# main.net
KiCad netlist of a schematic drawn in Altium Designer
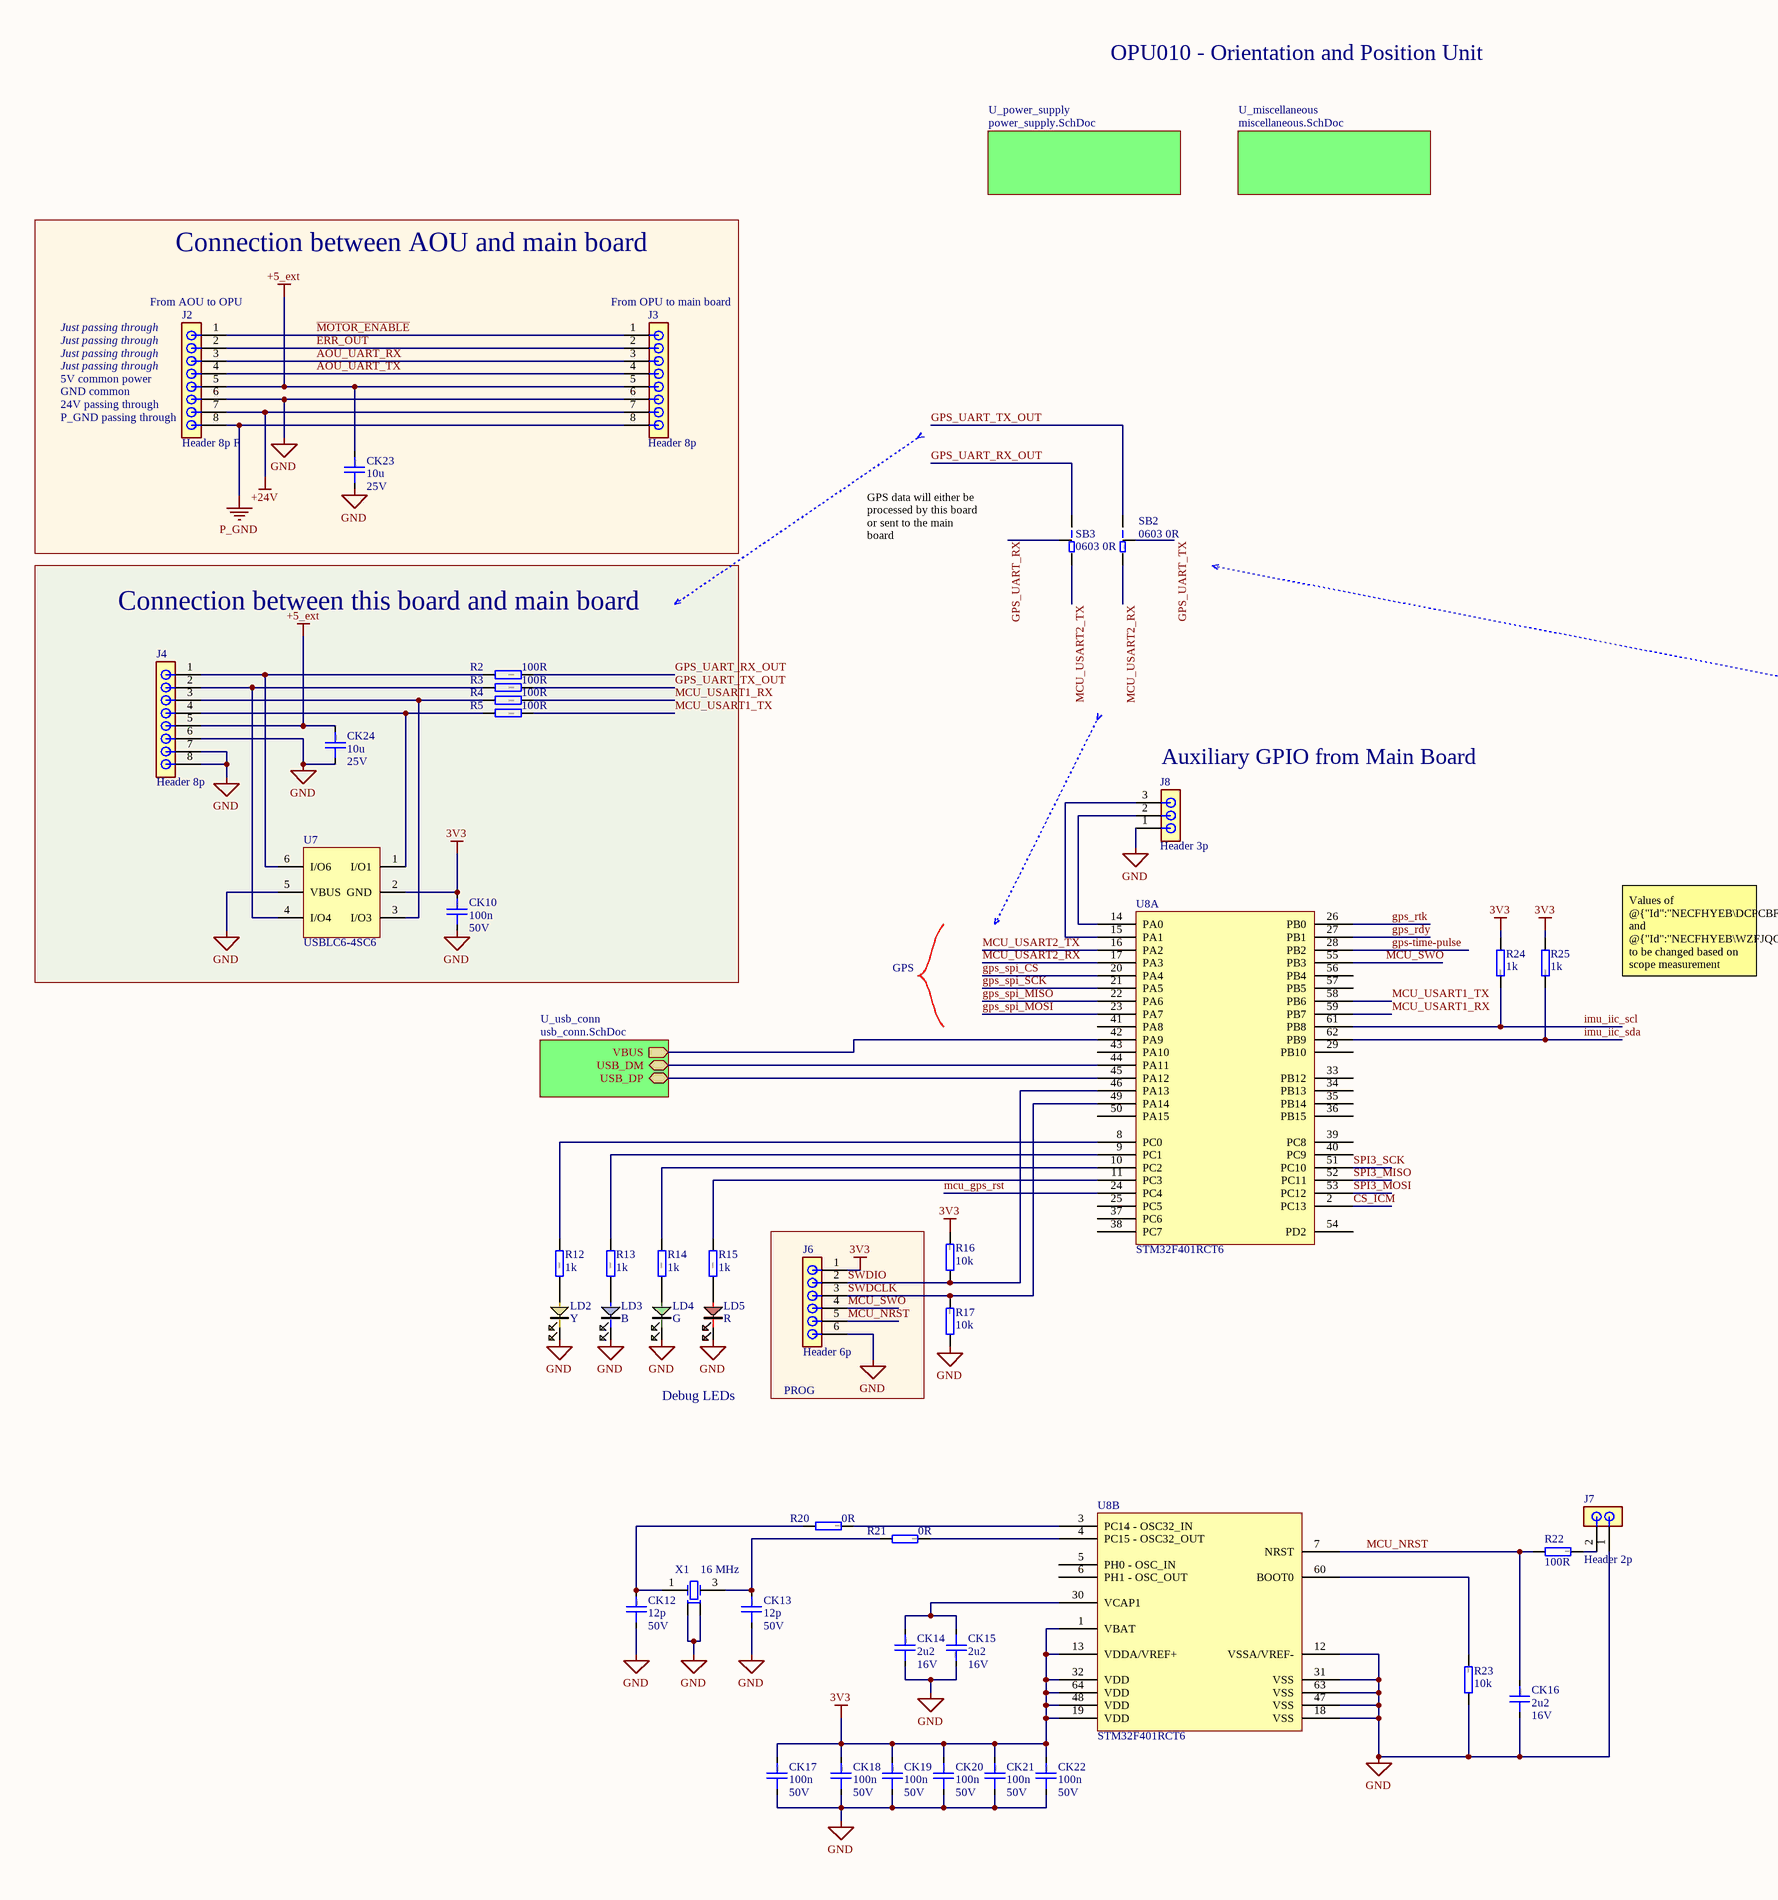
[diagram p0: main.SchDoc, left]
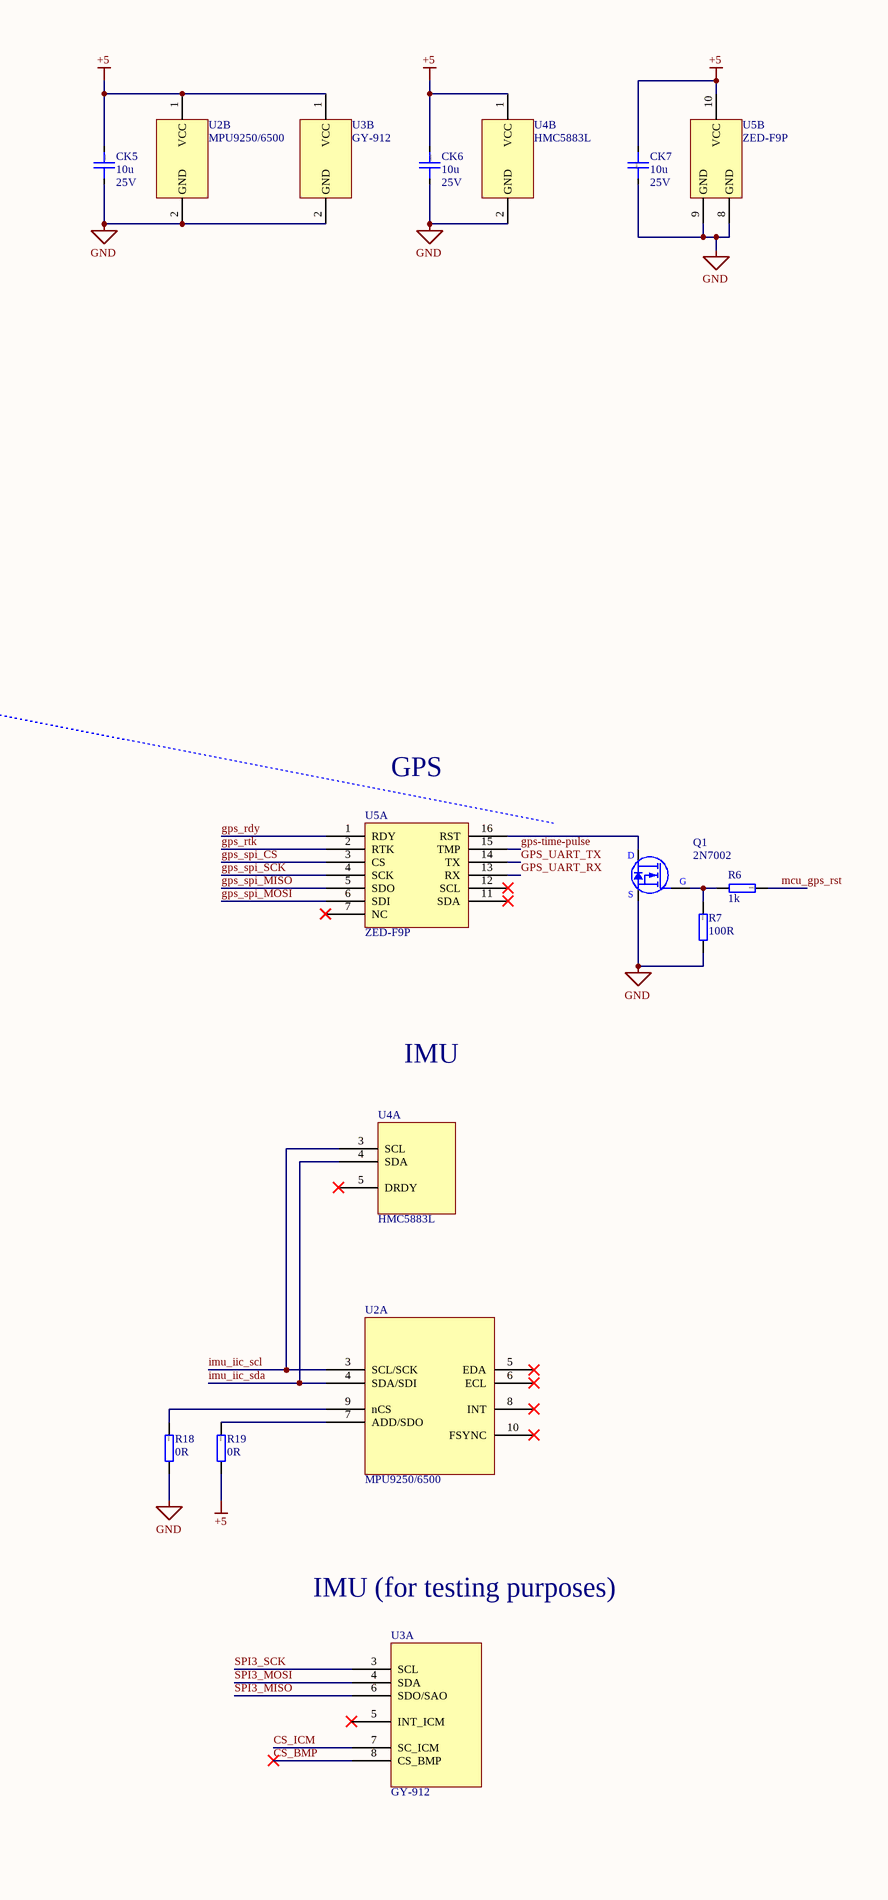
[diagram p1: main.SchDoc, right]

(export (version "E")
  (design (tool "Eeschema 10.0.6"))
  (components
    (comp (ref "CK5")
      (value "10u")
      (footprint "CAP0805")
      (description "25V 10uF X5R ±10% 0805 Multilayer Ceramic Capacitors MLCC - SMD/SMT ROHS")
      (fields (field (name "JLCPCB PART") "C15850") (field (name "VOLTAGE RATING") "25V"))
      (libsource (lib "Kubikova ultra knihovna") (part "Cap 10u 0805"))
    )
    (comp (ref "CK6")
      (value "10u")
      (footprint "CAP0805")
      (description "25V 10uF X5R ±10% 0805 Multilayer Ceramic Capacitors MLCC - SMD/SMT ROHS")
      (fields (field (name "JLCPCB PART") "C15850") (field (name "VOLTAGE RATING") "25V"))
      (libsource (lib "Kubikova ultra knihovna") (part "Cap 10u 0805"))
    )
    (comp (ref "CK7")
      (value "10u")
      (footprint "CAP0805")
      (description "25V 10uF X5R ±10% 0805 Multilayer Ceramic Capacitors MLCC - SMD/SMT ROHS")
      (fields (field (name "JLCPCB PART") "C15850") (field (name "VOLTAGE RATING") "25V"))
      (libsource (lib "Kubikova ultra knihovna") (part "Cap 10u 0805"))
    )
    (comp (ref "CK10")
      (value "100n")
      (footprint "CAP0603")
      (description "50V 100nF X7R ±10% 0603 Multilayer Ceramic Capacitors MLCC - SMD/SMT ROHS")
      (fields (field (name "JLCPCB PART") "C14663") (field (name "VOLTAGE RATING") "50V"))
      (libsource (lib "Kubikova ultra knihovna") (part "Cap 100n 0603"))
    )
    (comp (ref "CK12")
      (value "12p")
      (footprint "CAP0603")
      (description "50V 12pF C0G ±5% 0603 Multilayer Ceramic Capacitors MLCC - SMD/SMT ROHS")
      (fields (field (name "JLCPCB PART") "C38523") (field (name "VOLTAGE RATING") "50V"))
      (libsource (lib "Kubikova ultra knihovna") (part "Cap 12p 0603"))
    )
    (comp (ref "CK13")
      (value "12p")
      (footprint "CAP0603")
      (description "50V 12pF C0G ±5% 0603 Multilayer Ceramic Capacitors MLCC - SMD/SMT ROHS")
      (fields (field (name "JLCPCB PART") "C38523") (field (name "VOLTAGE RATING") "50V"))
      (libsource (lib "Kubikova ultra knihovna") (part "Cap 12p 0603"))
    )
    (comp (ref "CK14")
      (value "2u2")
      (footprint "CAP0603")
      (description "16V 2.2uF X5R ±10% 0603 Multilayer Ceramic Capacitors MLCC - SMD/SMT ROHS")
      (fields (field (name "JLCPCB PART") "C23630") (field (name "VOLTAGE RATING") "16V"))
      (libsource (lib "Kubikova ultra knihovna") (part "Cap 2u2 0603"))
    )
    (comp (ref "CK15")
      (value "2u2")
      (footprint "CAP0603")
      (description "16V 2.2uF X5R ±10% 0603 Multilayer Ceramic Capacitors MLCC - SMD/SMT ROHS")
      (fields (field (name "JLCPCB PART") "C23630") (field (name "VOLTAGE RATING") "16V"))
      (libsource (lib "Kubikova ultra knihovna") (part "Cap 2u2 0603"))
    )
    (comp (ref "CK16")
      (value "2u2")
      (footprint "CAP0603")
      (description "16V 2.2uF X5R ±10% 0603 Multilayer Ceramic Capacitors MLCC - SMD/SMT ROHS")
      (fields (field (name "JLCPCB PART") "C23630") (field (name "VOLTAGE RATING") "16V"))
      (libsource (lib "Kubikova ultra knihovna") (part "Cap 2u2 0603"))
    )
    (comp (ref "CK17")
      (value "100n")
      (footprint "CAP0603")
      (description "50V 100nF X7R ±10% 0603 Multilayer Ceramic Capacitors MLCC - SMD/SMT ROHS")
      (fields (field (name "JLCPCB PART") "C14663") (field (name "VOLTAGE RATING") "50V"))
      (libsource (lib "Kubikova ultra knihovna") (part "Cap 100n 0603"))
    )
    (comp (ref "CK18")
      (value "100n")
      (footprint "CAP0603")
      (description "50V 100nF X7R ±10% 0603 Multilayer Ceramic Capacitors MLCC - SMD/SMT ROHS")
      (fields (field (name "JLCPCB PART") "C14663") (field (name "VOLTAGE RATING") "50V"))
      (libsource (lib "Kubikova ultra knihovna") (part "Cap 100n 0603"))
    )
    (comp (ref "CK19")
      (value "100n")
      (footprint "CAP0603")
      (description "50V 100nF X7R ±10% 0603 Multilayer Ceramic Capacitors MLCC - SMD/SMT ROHS")
      (fields (field (name "JLCPCB PART") "C14663") (field (name "VOLTAGE RATING") "50V"))
      (libsource (lib "Kubikova ultra knihovna") (part "Cap 100n 0603"))
    )
    (comp (ref "CK20")
      (value "100n")
      (footprint "CAP0603")
      (description "50V 100nF X7R ±10% 0603 Multilayer Ceramic Capacitors MLCC - SMD/SMT ROHS")
      (fields (field (name "JLCPCB PART") "C14663") (field (name "VOLTAGE RATING") "50V"))
      (libsource (lib "Kubikova ultra knihovna") (part "Cap 100n 0603"))
    )
    (comp (ref "CK21")
      (value "100n")
      (footprint "CAP0603")
      (description "50V 100nF X7R ±10% 0603 Multilayer Ceramic Capacitors MLCC - SMD/SMT ROHS")
      (fields (field (name "JLCPCB PART") "C14663") (field (name "VOLTAGE RATING") "50V"))
      (libsource (lib "Kubikova ultra knihovna") (part "Cap 100n 0603"))
    )
    (comp (ref "CK22")
      (value "100n")
      (footprint "CAP0603")
      (description "50V 100nF X7R ±10% 0603 Multilayer Ceramic Capacitors MLCC - SMD/SMT ROHS")
      (fields (field (name "JLCPCB PART") "C14663") (field (name "VOLTAGE RATING") "50V"))
      (libsource (lib "Kubikova ultra knihovna") (part "Cap 100n 0603"))
    )
    (comp (ref "CK23")
      (value "10u")
      (footprint "CAP0805")
      (description "25V 10uF X5R ±10% 0805 Multilayer Ceramic Capacitors MLCC - SMD/SMT ROHS")
      (fields (field (name "JLCPCB PART") "C15850") (field (name "VOLTAGE RATING") "25V"))
      (libsource (lib "Kubikova ultra knihovna") (part "Cap 10u 0805"))
    )
    (comp (ref "CK24")
      (value "10u")
      (footprint "CAP0805")
      (description "25V 10uF X5R ±10% 0805 Multilayer Ceramic Capacitors MLCC - SMD/SMT ROHS")
      (fields (field (name "JLCPCB PART") "C15850") (field (name "VOLTAGE RATING") "25V"))
      (libsource (lib "Kubikova ultra knihovna") (part "Cap 10u 0805"))
    )
    (comp (ref "J2")
      (value "Header 8p F")
      (footprint "Pin header 8p - F")
      (fields (field (name "MANUFACTURER_PART_NUMBER") "DS1021-1*2SF11-B"))
      (libsource (lib "Kubikova ultra knihovna") (part "Pin header 8p_F"))
    )
    (comp (ref "J3")
      (value "Header 8p")
      (footprint "Pin header 8p")
      (fields
        (field (name "MANUFACTURER_PART_NUMBER") "DS1021-1*2SF11-B")
        (field (name "JLCPCB PART") "C37208")
      )
      (libsource (lib "Kubikova ultra knihovna") (part "Pin header 8p"))
    )
    (comp (ref "J4")
      (value "Header 8p")
      (footprint "Pin header 8p")
      (fields
        (field (name "MANUFACTURER_PART_NUMBER") "DS1021-1*2SF11-B")
        (field (name "JLCPCB PART") "C37208")
      )
      (libsource (lib "") (part "Pin header 8p_1"))
    )
    (comp (ref "J6")
      (value "Header 6p")
      (footprint "Pin header 6p")
      (fields
        (field (name "MANUFACTURER_PART_NUMBER") "DS1021-1*2SF11-B")
        (field (name "JLCPCB PART") "C37208")
      )
      (libsource (lib "Kubikova ultra knihovna") (part "Pin header 6p"))
    )
    (comp (ref "J7")
      (value "Header 2p")
      (footprint "Pin header 2p")
      (description "Connector")
      (fields
        (field (name "MANUFACTURER_PART_NUMBER") "DS1021-1*2SF11-B")
        (field (name "JLCPCB PART") "C492401")
      )
      (libsource (lib "Kubikova ultra knihovna") (part "Pin header 2p"))
    )
    (comp (ref "J8")
      (value "Header 3p")
      (footprint "Pin header 3p")
      (description "Direct Insert 2.54mm Policy 3A 2.5mm -40℃~+105℃ 3mm 6mm 250V Black 1x3P Single Row 3P Pin Headers")
      (fields
        (field (name "MANUFACTURER_PART_NUMBER") "DS1021-1*2SF11-B")
        (field (name "JLCPCB PART") "C2937625")
      )
      (libsource (lib "Kubikova ultra knihovna") (part "Pin header 3p"))
    )
    (comp (ref "LD2")
      (value "Y")
      (footprint "0603_LED_Y")
      (description "0603 Yellow Led")
      (fields (field (name "JLCPCB PART") "C7496811"))
      (libsource (lib "Kubikova ultra knihovna") (part "LED Y 0603"))
    )
    (comp (ref "LD3")
      (value "B")
      (footprint "0603_LED_B")
      (description "0603 Blue Led")
      (fields (field (name "JLCPCB PART") "C7496819"))
      (libsource (lib "Kubikova ultra knihovna") (part "LED B 0603"))
    )
    (comp (ref "LD4")
      (value "G")
      (footprint "0603_LED_G")
      (description "0603 Green Led")
      (fields (field (name "JLCPCB PART") "C22371297"))
      (libsource (lib "Kubikova ultra knihovna") (part "LED G 0603"))
    )
    (comp (ref "LD5")
      (value "R")
      (footprint "0603_LED_R")
      (description "-40℃~+85℃ Red 0603 LED Indication - Discrete ROHS")
      (fields (field (name "JLCPCB PART") "C2286"))
      (libsource (lib "Kubikova ultra knihovna") (part "LED R 0603"))
    )
    (comp (ref "Q1")
      (value "2N7002")
      (footprint "SOT95P230X110-3N(SOT23)")
      (description "60V 115mA 200mW 7.5Ω@10V,500mA 2.5V@250uA 1 N-Channel SOT-23 MOSFETs ROHS")
      (fields (field (name "JLCPCB PART") "C8545"))
      (libsource (lib "Kubikova ultra knihovna") (part "2N7002"))
    )
    (comp (ref "R2")
      (value "100R")
      (footprint "RESC2012X06N(SMR0805)")
      (description "125mW Thick Film Resistors 150V ±100ppm/℃ ±1% 100Ω 0805 Chip Resistor - Surface Mount ROHS")
      (fields (field (name "JLCPCB PART") "C17408") (field (name "AUTHOR") "JP/27.03.2014"))
      (libsource (lib "Kubikova ultra knihovna") (part "Res 100R 0805"))
    )
    (comp (ref "R3")
      (value "100R")
      (footprint "RESC2012X06N(SMR0805)")
      (description "125mW Thick Film Resistors 150V ±100ppm/℃ ±1% 100Ω 0805 Chip Resistor - Surface Mount ROHS")
      (fields (field (name "JLCPCB PART") "C17408") (field (name "AUTHOR") "JP/27.03.2014"))
      (libsource (lib "Kubikova ultra knihovna") (part "Res 100R 0805"))
    )
    (comp (ref "R4")
      (value "100R")
      (footprint "RESC2012X06N(SMR0805)")
      (description "125mW Thick Film Resistors 150V ±100ppm/℃ ±1% 100Ω 0805 Chip Resistor - Surface Mount ROHS")
      (fields (field (name "JLCPCB PART") "C17408") (field (name "AUTHOR") "JP/27.03.2014"))
      (libsource (lib "Kubikova ultra knihovna") (part "Res 100R 0805"))
    )
    (comp (ref "R5")
      (value "100R")
      (footprint "RESC2012X06N(SMR0805)")
      (description "125mW Thick Film Resistors 150V ±100ppm/℃ ±1% 100Ω 0805 Chip Resistor - Surface Mount ROHS")
      (fields (field (name "JLCPCB PART") "C17408") (field (name "AUTHOR") "JP/27.03.2014"))
      (libsource (lib "Kubikova ultra knihovna") (part "Res 100R 0805"))
    )
    (comp (ref "R6")
      (value "1k")
      (footprint "RESC2012X06N(SMR0805)")
      (description "125mW Thick Film Resistors 150V ±100ppm/℃ ±1% 1kΩ 0805 Chip Resistor - Surface Mount ROHS")
      (fields (field (name "JLCPCB PART") "C17513") (field (name "AUTHOR") "JP/27.03.2014"))
      (libsource (lib "Kubikova ultra knihovna") (part "Res 1k 0805"))
    )
    (comp (ref "R7")
      (value "100R")
      (footprint "RESC2012X06N(SMR0805)")
      (description "125mW Thick Film Resistors 150V ±100ppm/℃ ±1% 100Ω 0805 Chip Resistor - Surface Mount ROHS")
      (fields (field (name "JLCPCB PART") "C17408") (field (name "AUTHOR") "JP/27.03.2014"))
      (libsource (lib "Kubikova ultra knihovna") (part "Res 100R 0805"))
    )
    (comp (ref "R12")
      (value "1k")
      (footprint "RESC2012X06N(SMR0805)")
      (description "125mW Thick Film Resistors 150V ±100ppm/℃ ±1% 1kΩ 0805 Chip Resistor - Surface Mount ROHS")
      (fields (field (name "JLCPCB PART") "C17513") (field (name "AUTHOR") "JP/27.03.2014"))
      (libsource (lib "Kubikova ultra knihovna") (part "Res 1k 0805"))
    )
    (comp (ref "R13")
      (value "1k")
      (footprint "RESC2012X06N(SMR0805)")
      (description "125mW Thick Film Resistors 150V ±100ppm/℃ ±1% 1kΩ 0805 Chip Resistor - Surface Mount ROHS")
      (fields (field (name "JLCPCB PART") "C17513") (field (name "AUTHOR") "JP/27.03.2014"))
      (libsource (lib "Kubikova ultra knihovna") (part "Res 1k 0805"))
    )
    (comp (ref "R14")
      (value "1k")
      (footprint "RESC2012X06N(SMR0805)")
      (description "125mW Thick Film Resistors 150V ±100ppm/℃ ±1% 1kΩ 0805 Chip Resistor - Surface Mount ROHS")
      (fields (field (name "JLCPCB PART") "C17513") (field (name "AUTHOR") "JP/27.03.2014"))
      (libsource (lib "Kubikova ultra knihovna") (part "Res 1k 0805"))
    )
    (comp (ref "R15")
      (value "1k")
      (footprint "RESC2012X06N(SMR0805)")
      (description "125mW Thick Film Resistors 150V ±100ppm/℃ ±1% 1kΩ 0805 Chip Resistor - Surface Mount ROHS")
      (fields (field (name "JLCPCB PART") "C17513") (field (name "AUTHOR") "JP/27.03.2014"))
      (libsource (lib "Kubikova ultra knihovna") (part "Res 1k 0805"))
    )
    (comp (ref "R16")
      (value "10k")
      (footprint "RESC2012X06N(SMR0805)")
      (description "125mW Thick Film Resistors 150V ±100ppm/℃ ±1% 10kΩ 0805 Chip Resistor - Surface Mount ROHS")
      (fields (field (name "JLCPCB PART") "C17414"))
      (libsource (lib "Kubikova ultra knihovna") (part "Res 10k 0805"))
    )
    (comp (ref "R17")
      (value "10k")
      (footprint "RESC2012X06N(SMR0805)")
      (description "125mW Thick Film Resistors 150V ±100ppm/℃ ±1% 10kΩ 0805 Chip Resistor - Surface Mount ROHS")
      (fields (field (name "JLCPCB PART") "C17414"))
      (libsource (lib "Kubikova ultra knihovna") (part "Res 10k 0805"))
    )
    (comp (ref "R18")
      (value "0R")
      (footprint "RESC2012X06N(SMR0805)")
      (description "125mW Thick Film Resistors 150V ±800ppm/℃ ±1% 0Ω 0805 Chip Resistor - Surface Mount ROHS")
      (fields (field (name "JLCPCB PART") "C17477") (field (name "AUTHOR") "JP/27.03.2014"))
      (libsource (lib "Kubikova ultra knihovna") (part "Res 0R 0805"))
    )
    (comp (ref "R19")
      (value "0R")
      (footprint "RESC2012X06N(SMR0805)")
      (description "125mW Thick Film Resistors 150V ±800ppm/℃ ±1% 0Ω 0805 Chip Resistor - Surface Mount ROHS")
      (fields (field (name "JLCPCB PART") "C17477") (field (name "AUTHOR") "JP/27.03.2014"))
      (libsource (lib "Kubikova ultra knihovna") (part "Res 0R 0805"))
    )
    (comp (ref "R20")
      (value "0R")
      (footprint "RESC2012X06N(SMR0805)")
      (description "125mW Thick Film Resistors 150V ±800ppm/℃ ±1% 0Ω 0805 Chip Resistor - Surface Mount ROHS")
      (fields (field (name "JLCPCB PART") "C17477") (field (name "AUTHOR") "JP/27.03.2014"))
      (libsource (lib "Kubikova ultra knihovna") (part "Res 0R 0805"))
    )
    (comp (ref "R21")
      (value "0R")
      (footprint "RESC2012X06N(SMR0805)")
      (description "125mW Thick Film Resistors 150V ±800ppm/℃ ±1% 0Ω 0805 Chip Resistor - Surface Mount ROHS")
      (fields (field (name "JLCPCB PART") "C17477") (field (name "AUTHOR") "JP/27.03.2014"))
      (libsource (lib "Kubikova ultra knihovna") (part "Res 0R 0805"))
    )
    (comp (ref "R22")
      (value "100R")
      (footprint "RESC2012X06N(SMR0805)")
      (description "125mW Thick Film Resistors 150V ±100ppm/℃ ±1% 100Ω 0805 Chip Resistor - Surface Mount ROHS")
      (fields (field (name "JLCPCB PART") "C17408") (field (name "AUTHOR") "JP/27.03.2014"))
      (libsource (lib "Kubikova ultra knihovna") (part "Res 100R 0805"))
    )
    (comp (ref "R23")
      (value "10k")
      (footprint "RESC2012X06N(SMR0805)")
      (description "125mW Thick Film Resistors 150V ±100ppm/℃ ±1% 10kΩ 0805 Chip Resistor - Surface Mount ROHS")
      (fields (field (name "JLCPCB PART") "C17414"))
      (libsource (lib "Kubikova ultra knihovna") (part "Res 10k 0805"))
    )
    (comp (ref "R24")
      (value "1k")
      (footprint "RESC2012X06N(SMR0805)")
      (description "125mW Thick Film Resistors 150V ±100ppm/℃ ±1% 1kΩ 0805 Chip Resistor - Surface Mount ROHS")
      (fields (field (name "JLCPCB PART") "C17513") (field (name "AUTHOR") "JP/27.03.2014"))
      (libsource (lib "Kubikova ultra knihovna") (part "Res 1k 0805"))
    )
    (comp (ref "R25")
      (value "1k")
      (footprint "RESC2012X06N(SMR0805)")
      (description "125mW Thick Film Resistors 150V ±100ppm/℃ ±1% 1kΩ 0805 Chip Resistor - Surface Mount ROHS")
      (fields (field (name "JLCPCB PART") "C17513") (field (name "AUTHOR") "JP/27.03.2014"))
      (libsource (lib "Kubikova ultra knihovna") (part "Res 1k 0805"))
    )
    (comp (ref "SB2")
      (value "0603 0R")
      (footprint "Solder T bridge 0603")
      (fields (field (name "JLCPCB PART") "C21189"))
      (libsource (lib "Kubikova ultra knihovna") (part "0R T-junction"))
    )
    (comp (ref "SB3")
      (value "0603 0R")
      (footprint "Solder T bridge 0603")
      (fields (field (name "JLCPCB PART") "C21189"))
      (libsource (lib "Kubikova ultra knihovna") (part "0R T-junction"))
    )
    (comp (ref "U2")
      (value "MPU9250/6500")
      (footprint "devboard MPU9250/6500")
      (description "Module, MPU9250/6500")
      (libsource (lib "Kubikova ultra knihovna") (part "devboard MPU9250/6500"))
    )
    (comp (ref "U3")
      (value "GY-912")
      (footprint "devboard GY-912")
      (description "devboard GY-912")
      (libsource (lib "Kubikova ultra knihovna") (part "devboard GY-912"))
    )
    (comp (ref "U4")
      (value "HMC5883L")
      (footprint "devboard HMC5883L")
      (description "devboard HMC5883L")
      (libsource (lib "") (part "devboard HMC5883L_1"))
    )
    (comp (ref "U5")
      (value "ZED-F9P")
      (footprint "devboard gnss rtk click")
      (description "devboard GNSS RTK click")
      (libsource (lib "Kubikova ultra knihovna") (part "devboard ZED-F9P"))
    )
    (comp (ref "U7")
      (value "USBLC6-4SC6")
      (footprint "SOT23-6")
      (description "5A 17V 6V Unidirectional 5.25V SOT-23-6 ESD and Surge Protection (TVS/ESD) ROHS")
      (fields (field (name "JLCPCB PART") "C111212"))
      (libsource (lib "Kubikova ultra knihovna") (part "USBLC6-4SC6"))
    )
    (comp (ref "U8")
      (value "STM32F401RCT6")
      (footprint "LQFP64")
      (description "256KB 1.7V~3.6V ARM-M4 64KB 84MHz FLASH 50 LQFP-64(10x10) Microcontrollers (MCU/MPU/SOC) ROHS")
      (fields (field (name "JLCPCB PART") "C74524"))
      (libsource (lib "Kubikova ultra knihovna") (part "STM32F401RCT6"))
    )
    (comp (ref "X1")
      (value "16 MHz")
      (footprint "3225 XTal")
      (description "X322516MLB4SI\r\n16MHz Surface Mount Crystal 9pF ±10ppm ±20ppm SMD3225-4P Crystals ROHS")
      (libsource (lib "Kubikova ultra knihovna") (part "16 MHz crystal"))
    )
  )
  (nets
    (net (code "1") (name "+5") (class "Default")
      (node (ref "CK5") (pin "1") (pinfunction "1_1") (pintype "passive"))
      (node (ref "CK6") (pin "1") (pinfunction "1_1") (pintype "passive"))
      (node (ref "CK7") (pin "1") (pinfunction "1_1") (pintype "passive"))
      (node (ref "R19") (pin "1") (pinfunction "1_1") (pintype "passive"))
      (node (ref "U2") (pin "1") (pinfunction "VCC_1") (pintype "passive"))
      (node (ref "U3") (pin "1") (pinfunction "VCC_1") (pintype "passive"))
      (node (ref "U4") (pin "1") (pinfunction "VCC_1") (pintype "passive"))
      (node (ref "U5") (pin "10") (pinfunction "VCC_10") (pintype "passive"))
    )
    (net (code "2") (name "+5_ext") (class "Default")
      (node (ref "CK23") (pin "1") (pinfunction "1_1") (pintype "passive"))
      (node (ref "CK24") (pin "1") (pinfunction "1_1") (pintype "passive"))
      (node (ref "J2") (pin "5") (pinfunction "5_5") (pintype "passive"))
      (node (ref "J3") (pin "5") (pinfunction "5_5") (pintype "passive"))
      (node (ref "J4") (pin "5") (pinfunction "5_5") (pintype "passive"))
    )
    (net (code "3") (name "+24V") (class "Default")
      (node (ref "J2") (pin "7") (pinfunction "7_7") (pintype "passive"))
      (node (ref "J3") (pin "7") (pinfunction "7_7") (pintype "passive"))
    )
    (net (code "4") (name "/AOU_UART_RX") (class "Default")
      (node (ref "J2") (pin "3") (pinfunction "3_3") (pintype "passive"))
      (node (ref "J3") (pin "3") (pinfunction "3_3") (pintype "passive"))
    )
    (net (code "5") (name "/AOU_UART_TX") (class "Default")
      (node (ref "J2") (pin "4") (pinfunction "4_4") (pintype "passive"))
      (node (ref "J3") (pin "4") (pinfunction "4_4") (pintype "passive"))
    )
    (net (code "6") (name "/CS_BMP") (class "Default")
      (node (ref "U3") (pin "8") (pinfunction "CS_BMP_8") (pintype "passive+no_connect"))
    )
    (net (code "7") (name "/CS_ICM") (class "Default")
      (node (ref "U3") (pin "7") (pinfunction "SC_ICM_7") (pintype "passive"))
      (node (ref "U8") (pin "2") (pinfunction "PC13_2") (pintype "passive"))
    )
    (net (code "8") (name "/ERR_OUT") (class "Default")
      (node (ref "J2") (pin "2") (pinfunction "2_2") (pintype "passive"))
      (node (ref "J3") (pin "2") (pinfunction "2_2") (pintype "passive"))
    )
    (net (code "9") (name "/GPS_UART_RX") (class "Default")
      (node (ref "SB3") (pin "2") (pinfunction "2_2") (pintype "passive"))
      (node (ref "U5") (pin "13") (pinfunction "RX_13") (pintype "passive"))
    )
    (net (code "10") (name "/GPS_UART_RX_OUT") (class "Default")
      (node (ref "R2") (pin "2") (pinfunction "2_2") (pintype "passive"))
      (node (ref "SB3") (pin "1") (pinfunction "1_1") (pintype "passive"))
    )
    (net (code "11") (name "/GPS_UART_TX") (class "Default")
      (node (ref "SB2") (pin "2") (pinfunction "2_2") (pintype "passive"))
      (node (ref "U5") (pin "14") (pinfunction "TX_14") (pintype "passive"))
    )
    (net (code "12") (name "/GPS_UART_TX_OUT") (class "Default")
      (node (ref "R3") (pin "2") (pinfunction "2_2") (pintype "passive"))
      (node (ref "SB2") (pin "1") (pinfunction "1_1") (pintype "passive"))
    )
    (net (code "13") (name "/MCU_NRST") (class "Default")
      (node (ref "CK16") (pin "1") (pinfunction "1_1") (pintype "passive"))
      (node (ref "J6") (pin "5") (pinfunction "5_5") (pintype "passive"))
      (node (ref "R22") (pin "1") (pinfunction "1_1") (pintype "passive"))
      (node (ref "U8") (pin "7") (pinfunction "NRST_7") (pintype "passive"))
    )
    (net (code "14") (name "/MCU_SWO") (class "Default")
      (node (ref "J6") (pin "4") (pinfunction "4_4") (pintype "passive"))
      (node (ref "U8") (pin "55") (pinfunction "PB3_55") (pintype "passive"))
    )
    (net (code "15") (name "/MCU_USART1_RX") (class "Default")
      (node (ref "R4") (pin "2") (pinfunction "2_2") (pintype "passive"))
      (node (ref "U8") (pin "59") (pinfunction "PB7_59") (pintype "passive"))
    )
    (net (code "16") (name "/MCU_USART1_TX") (class "Default")
      (node (ref "R5") (pin "2") (pinfunction "2_2") (pintype "passive"))
      (node (ref "U8") (pin "58") (pinfunction "PB6_58") (pintype "passive"))
    )
    (net (code "17") (name "/MCU_USART2_RX") (class "Default")
      (node (ref "SB2") (pin "3") (pinfunction "3_3") (pintype "passive"))
      (node (ref "U8") (pin "17") (pinfunction "PA3_17") (pintype "passive"))
    )
    (net (code "18") (name "/MCU_USART2_TX") (class "Default")
      (node (ref "SB3") (pin "3") (pinfunction "3_3") (pintype "passive"))
      (node (ref "U8") (pin "16") (pinfunction "PA2_16") (pintype "passive"))
    )
    (net (code "19") (name "/SPI3_MISO") (class "Default")
      (node (ref "U3") (pin "6") (pinfunction "SDO/SAO_6") (pintype "passive"))
      (node (ref "U8") (pin "52") (pinfunction "PC11_52") (pintype "passive"))
    )
    (net (code "20") (name "/SPI3_MOSI") (class "Default")
      (node (ref "U3") (pin "4") (pinfunction "SDA_4") (pintype "passive"))
      (node (ref "U8") (pin "53") (pinfunction "PC12_53") (pintype "passive"))
    )
    (net (code "21") (name "/SPI3_SCK") (class "Default")
      (node (ref "U3") (pin "3") (pinfunction "SCL_3") (pintype "passive"))
      (node (ref "U8") (pin "51") (pinfunction "PC10_51") (pintype "passive"))
    )
    (net (code "22") (name "/SWDCLK") (class "Default")
      (node (ref "J6") (pin "3") (pinfunction "3_3") (pintype "passive"))
      (node (ref "R17") (pin "2") (pinfunction "2_2") (pintype "passive"))
      (node (ref "U8") (pin "49") (pinfunction "PA14_49") (pintype "passive"))
    )
    (net (code "23") (name "/SWDIO") (class "Default")
      (node (ref "J6") (pin "2") (pinfunction "2_2") (pintype "passive"))
      (node (ref "R16") (pin "1") (pinfunction "1_1") (pintype "passive"))
      (node (ref "U8") (pin "46") (pinfunction "PA13_46") (pintype "passive"))
    )
    (net (code "24") (name "/USB_DM") (class "Default")
      (node (ref "U8") (pin "44") (pinfunction "PA11_44") (pintype "passive"))
    )
    (net (code "25") (name "/USB_DP") (class "Default")
      (node (ref "U8") (pin "45") (pinfunction "PA12_45") (pintype "passive"))
    )
    (net (code "26") (name "/VBUS") (class "Default")
      (node (ref "U8") (pin "42") (pinfunction "PA9_42") (pintype "passive"))
    )
    (net (code "27") (name "/gps-time-pulse") (class "Default")
      (node (ref "U5") (pin "15") (pinfunction "TMP_15") (pintype "passive"))
      (node (ref "U8") (pin "28") (pinfunction "PB2_28") (pintype "passive"))
    )
    (net (code "28") (name "/gps_rdy") (class "Default")
      (node (ref "U5") (pin "1") (pinfunction "RDY_1") (pintype "passive"))
      (node (ref "U8") (pin "27") (pinfunction "PB1_27") (pintype "passive"))
    )
    (net (code "29") (name "/gps_rtk") (class "Default")
      (node (ref "U5") (pin "2") (pinfunction "RTK_2") (pintype "passive"))
      (node (ref "U8") (pin "26") (pinfunction "PB0_26") (pintype "passive"))
    )
    (net (code "30") (name "/gps_spi_CS") (class "Default")
      (node (ref "U5") (pin "3") (pinfunction "CS_3") (pintype "passive"))
      (node (ref "U8") (pin "20") (pinfunction "PA4_20") (pintype "passive"))
    )
    (net (code "31") (name "/gps_spi_MISO") (class "Default")
      (node (ref "U5") (pin "5") (pinfunction "SDO_5") (pintype "passive"))
      (node (ref "U8") (pin "22") (pinfunction "PA6_22") (pintype "passive"))
    )
    (net (code "32") (name "/gps_spi_MOSI") (class "Default")
      (node (ref "U5") (pin "6") (pinfunction "SDI_6") (pintype "passive"))
      (node (ref "U8") (pin "23") (pinfunction "PA7_23") (pintype "passive"))
    )
    (net (code "33") (name "/gps_spi_SCK") (class "Default")
      (node (ref "U5") (pin "4") (pinfunction "SCK_4") (pintype "passive"))
      (node (ref "U8") (pin "21") (pinfunction "PA5_21") (pintype "passive"))
    )
    (net (code "34") (name "/imu_iic_scl") (class "Default")
      (node (ref "R24") (pin "2") (pinfunction "2_2") (pintype "passive"))
      (node (ref "U2") (pin "3") (pinfunction "SCL/SCK_3") (pintype "passive"))
      (node (ref "U4") (pin "3") (pinfunction "SCL_3") (pintype "passive"))
      (node (ref "U8") (pin "61") (pinfunction "PB8_61") (pintype "passive"))
    )
    (net (code "35") (name "/imu_iic_sda") (class "Default")
      (node (ref "R25") (pin "2") (pinfunction "2_2") (pintype "passive"))
      (node (ref "U2") (pin "4") (pinfunction "SDA/SDI_4") (pintype "passive"))
      (node (ref "U4") (pin "4") (pinfunction "SDA_4") (pintype "passive"))
      (node (ref "U8") (pin "62") (pinfunction "PB9_62") (pintype "passive"))
    )
    (net (code "36") (name "/mcu_gps_rst") (class "Default")
      (node (ref "R6") (pin "2") (pinfunction "2_2") (pintype "passive"))
      (node (ref "U8") (pin "24") (pinfunction "PC4_24") (pintype "passive"))
    )
    (net (code "37") (name "/~{MOTOR_ENABLE}") (class "Default")
      (node (ref "J2") (pin "1") (pinfunction "1_1") (pintype "passive"))
      (node (ref "J3") (pin "1") (pinfunction "1_1") (pintype "passive"))
    )
    (net (code "38") (name "3V3") (class "Default")
      (node (ref "CK10") (pin "1") (pinfunction "1_1") (pintype "passive"))
      (node (ref "CK17") (pin "1") (pinfunction "1_1") (pintype "passive"))
      (node (ref "CK18") (pin "1") (pinfunction "1_1") (pintype "passive"))
      (node (ref "CK19") (pin "1") (pinfunction "1_1") (pintype "passive"))
      (node (ref "CK20") (pin "1") (pinfunction "1_1") (pintype "passive"))
      (node (ref "CK21") (pin "1") (pinfunction "1_1") (pintype "passive"))
      (node (ref "CK22") (pin "1") (pinfunction "1_1") (pintype "passive"))
      (node (ref "J6") (pin "1") (pinfunction "1_1") (pintype "passive"))
      (node (ref "R16") (pin "2") (pinfunction "2_2") (pintype "passive"))
      (node (ref "R24") (pin "1") (pinfunction "1_1") (pintype "passive"))
      (node (ref "R25") (pin "1") (pinfunction "1_1") (pintype "passive"))
      (node (ref "U7") (pin "2") (pinfunction "GND_2") (pintype "passive"))
      (node (ref "U8") (pin "1") (pinfunction "VBAT_1") (pintype "passive"))
      (node (ref "U8") (pin "13") (pinfunction "VDDA/VREF+_13") (pintype "passive"))
      (node (ref "U8") (pin "19") (pinfunction "VDD_19") (pintype "passive"))
      (node (ref "U8") (pin "32") (pinfunction "VDD_32") (pintype "passive"))
      (node (ref "U8") (pin "48") (pinfunction "VDD_48") (pintype "passive"))
      (node (ref "U8") (pin "64") (pinfunction "VDD_64") (pintype "passive"))
    )
    (net (code "39") (name "GND") (class "Default")
      (node (ref "CK10") (pin "2") (pinfunction "2_2") (pintype "passive"))
      (node (ref "CK12") (pin "2") (pinfunction "2_2") (pintype "passive"))
      (node (ref "CK13") (pin "2") (pinfunction "2_2") (pintype "passive"))
      (node (ref "CK14") (pin "2") (pinfunction "2_2") (pintype "passive"))
      (node (ref "CK15") (pin "1") (pinfunction "1_1") (pintype "passive"))
      (node (ref "CK16") (pin "2") (pinfunction "2_2") (pintype "passive"))
      (node (ref "CK17") (pin "2") (pinfunction "2_2") (pintype "passive"))
      (node (ref "CK18") (pin "2") (pinfunction "2_2") (pintype "passive"))
      (node (ref "CK19") (pin "2") (pinfunction "2_2") (pintype "passive"))
      (node (ref "CK20") (pin "2") (pinfunction "2_2") (pintype "passive"))
      (node (ref "CK21") (pin "2") (pinfunction "2_2") (pintype "passive"))
      (node (ref "CK22") (pin "2") (pinfunction "2_2") (pintype "passive"))
      (node (ref "CK23") (pin "2") (pinfunction "2_2") (pintype "passive"))
      (node (ref "CK24") (pin "2") (pinfunction "2_2") (pintype "passive"))
      (node (ref "CK5") (pin "2") (pinfunction "2_2") (pintype "passive"))
      (node (ref "CK6") (pin "2") (pinfunction "2_2") (pintype "passive"))
      (node (ref "CK7") (pin "2") (pinfunction "2_2") (pintype "passive"))
      (node (ref "J2") (pin "6") (pinfunction "6_6") (pintype "passive"))
      (node (ref "J3") (pin "6") (pinfunction "6_6") (pintype "passive"))
      (node (ref "J4") (pin "6") (pinfunction "6_6") (pintype "passive"))
      (node (ref "J4") (pin "7") (pinfunction "7_7") (pintype "passive"))
      (node (ref "J4") (pin "8") (pinfunction "8_8") (pintype "passive"))
      (node (ref "J6") (pin "6") (pinfunction "6_6") (pintype "passive"))
      (node (ref "J7") (pin "1") (pinfunction "1_1") (pintype "passive"))
      (node (ref "J8") (pin "1") (pinfunction "1_1") (pintype "passive"))
      (node (ref "LD2") (pin "2") (pintype "passive"))
      (node (ref "LD3") (pin "2") (pintype "passive"))
      (node (ref "LD4") (pin "2") (pintype "passive"))
      (node (ref "LD5") (pin "2") (pintype "passive"))
      (node (ref "Q1") (pin "2") (pinfunction "S_2") (pintype "passive"))
      (node (ref "R17") (pin "1") (pinfunction "1_1") (pintype "passive"))
      (node (ref "R18") (pin "1") (pinfunction "1_1") (pintype "passive"))
      (node (ref "R23") (pin "1") (pinfunction "1_1") (pintype "passive"))
      (node (ref "R7") (pin "1") (pinfunction "1_1") (pintype "passive"))
      (node (ref "U2") (pin "2") (pinfunction "GND_2") (pintype "passive"))
      (node (ref "U3") (pin "2") (pinfunction "GND_2") (pintype "passive"))
      (node (ref "U4") (pin "2") (pinfunction "GND_2") (pintype "passive"))
      (node (ref "U5") (pin "8") (pinfunction "GND_8") (pintype "passive"))
      (node (ref "U5") (pin "9") (pinfunction "GND_9") (pintype "passive"))
      (node (ref "U7") (pin "5") (pinfunction "VBUS_5") (pintype "passive"))
      (node (ref "U8") (pin "12") (pinfunction "VSSA/VREF-_12") (pintype "passive"))
      (node (ref "U8") (pin "18") (pinfunction "VSS_18") (pintype "passive"))
      (node (ref "U8") (pin "31") (pinfunction "VSS_31") (pintype "passive"))
      (node (ref "U8") (pin "47") (pinfunction "VSS_47") (pintype "passive"))
      (node (ref "U8") (pin "63") (pinfunction "VSS_63") (pintype "passive"))
      (node (ref "X1") (pin "2") (pinfunction "2_2") (pintype "passive"))
      (node (ref "X1") (pin "4") (pinfunction "4_4") (pintype "passive"))
    )
    (net (code "40") (name "Net-(CK12-Pad1)") (class "Default")
      (node (ref "CK12") (pin "1") (pinfunction "1_1") (pintype "passive"))
      (node (ref "R20") (pin "1") (pinfunction "1_1") (pintype "passive"))
      (node (ref "X1") (pin "1") (pinfunction "1_1") (pintype "passive"))
    )
    (net (code "41") (name "Net-(CK13-Pad1)") (class "Default")
      (node (ref "CK13") (pin "1") (pinfunction "1_1") (pintype "passive"))
      (node (ref "R21") (pin "1") (pinfunction "1_1") (pintype "passive"))
      (node (ref "X1") (pin "3") (pinfunction "3_3") (pintype "passive"))
    )
    (net (code "42") (name "Net-(J7-Pad2)") (class "Default")
      (node (ref "J7") (pin "2") (pinfunction "2_2") (pintype "passive"))
      (node (ref "R22") (pin "2") (pinfunction "2_2") (pintype "passive"))
    )
    (net (code "43") (name "Net-(LD2-Pad1)") (class "Default")
      (node (ref "LD2") (pin "1") (pintype "passive"))
      (node (ref "R12") (pin "2") (pinfunction "2_2") (pintype "passive"))
    )
    (net (code "44") (name "Net-(LD3-Pad1)") (class "Default")
      (node (ref "LD3") (pin "1") (pintype "passive"))
      (node (ref "R13") (pin "2") (pinfunction "2_2") (pintype "passive"))
    )
    (net (code "45") (name "Net-(LD4-Pad1)") (class "Default")
      (node (ref "LD4") (pin "1") (pintype "passive"))
      (node (ref "R14") (pin "2") (pinfunction "2_2") (pintype "passive"))
    )
    (net (code "46") (name "Net-(LD5-Pad1)") (class "Default")
      (node (ref "LD5") (pin "1") (pintype "passive"))
      (node (ref "R15") (pin "2") (pinfunction "2_2") (pintype "passive"))
    )
    (net (code "47") (name "Net-(Q1-D)") (class "Default")
      (node (ref "Q1") (pin "3") (pinfunction "D_3") (pintype "passive"))
      (node (ref "U5") (pin "16") (pinfunction "RST_16") (pintype "passive"))
    )
    (net (code "48") (name "Net-(Q1-G)") (class "Default")
      (node (ref "Q1") (pin "1") (pinfunction "G_1") (pintype "passive"))
      (node (ref "R6") (pin "1") (pinfunction "1_1") (pintype "passive"))
      (node (ref "R7") (pin "2") (pinfunction "2_2") (pintype "passive"))
    )
    (net (code "49") (name "Net-(U2A-ADD{slash}SDO)") (class "Default")
      (node (ref "R19") (pin "2") (pinfunction "2_2") (pintype "passive"))
      (node (ref "U2") (pin "7") (pinfunction "ADD/SDO_7") (pintype "passive"))
    )
    (net (code "50") (name "Net-(U2A-nCS)") (class "Default")
      (node (ref "R18") (pin "2") (pinfunction "2_2") (pintype "passive"))
      (node (ref "U2") (pin "9") (pinfunction "nCS_9") (pintype "passive"))
    )
    (net (code "51") (name "Net-(U7-I{slash}O1)") (class "Default")
      (node (ref "J4") (pin "4") (pinfunction "4_4") (pintype "passive"))
      (node (ref "R5") (pin "1") (pinfunction "1_1") (pintype "passive"))
      (node (ref "U7") (pin "1") (pinfunction "I/O1_1") (pintype "passive"))
    )
    (net (code "52") (name "Net-(U7-I{slash}O3)") (class "Default")
      (node (ref "J4") (pin "3") (pinfunction "3_3") (pintype "passive"))
      (node (ref "R4") (pin "1") (pinfunction "1_1") (pintype "passive"))
      (node (ref "U7") (pin "3") (pinfunction "I/O3_3") (pintype "passive"))
    )
    (net (code "53") (name "Net-(U7-I{slash}O4)") (class "Default")
      (node (ref "J4") (pin "2") (pinfunction "2_2") (pintype "passive"))
      (node (ref "R3") (pin "1") (pinfunction "1_1") (pintype "passive"))
      (node (ref "U7") (pin "4") (pinfunction "I/O4_4") (pintype "passive"))
    )
    (net (code "54") (name "Net-(U7-I{slash}O6)") (class "Default")
      (node (ref "J4") (pin "1") (pinfunction "1_1") (pintype "passive"))
      (node (ref "R2") (pin "1") (pinfunction "1_1") (pintype "passive"))
      (node (ref "U7") (pin "6") (pinfunction "I/O6_6") (pintype "passive"))
    )
    (net (code "55") (name "Net-(U8A-PA0)") (class "Default")
      (node (ref "J8") (pin "2") (pinfunction "2_2") (pintype "passive"))
      (node (ref "U8") (pin "14") (pinfunction "PA0_14") (pintype "passive"))
    )
    (net (code "56") (name "Net-(U8A-PA1)") (class "Default")
      (node (ref "J8") (pin "3") (pinfunction "3_3") (pintype "passive"))
      (node (ref "U8") (pin "15") (pinfunction "PA1_15") (pintype "passive"))
    )
    (net (code "57") (name "Net-(U8A-PC0)") (class "Default")
      (node (ref "R12") (pin "1") (pinfunction "1_1") (pintype "passive"))
      (node (ref "U8") (pin "8") (pinfunction "PC0_8") (pintype "passive"))
    )
    (net (code "58") (name "Net-(U8A-PC1)") (class "Default")
      (node (ref "R13") (pin "1") (pinfunction "1_1") (pintype "passive"))
      (node (ref "U8") (pin "9") (pinfunction "PC1_9") (pintype "passive"))
    )
    (net (code "59") (name "Net-(U8A-PC2)") (class "Default")
      (node (ref "R14") (pin "1") (pinfunction "1_1") (pintype "passive"))
      (node (ref "U8") (pin "10") (pinfunction "PC2_10") (pintype "passive"))
    )
    (net (code "60") (name "Net-(U8A-PC3)") (class "Default")
      (node (ref "R15") (pin "1") (pinfunction "1_1") (pintype "passive"))
      (node (ref "U8") (pin "11") (pinfunction "PC3_11") (pintype "passive"))
    )
    (net (code "61") (name "Net-(U8B-BOOT0)") (class "Default")
      (node (ref "R23") (pin "2") (pinfunction "2_2") (pintype "passive"))
      (node (ref "U8") (pin "60") (pinfunction "BOOT0_60") (pintype "passive"))
    )
    (net (code "62") (name "Net-(U8B-PC14_-_OSC32_IN)") (class "Default")
      (node (ref "R20") (pin "2") (pinfunction "2_2") (pintype "passive"))
      (node (ref "U8") (pin "3") (pinfunction "PC14_-_OSC32_IN_3") (pintype "passive"))
    )
    (net (code "63") (name "Net-(U8B-PC15_-_OSC32_OUT)") (class "Default")
      (node (ref "R21") (pin "2") (pinfunction "2_2") (pintype "passive"))
      (node (ref "U8") (pin "4") (pinfunction "PC15_-_OSC32_OUT_4") (pintype "passive"))
    )
    (net (code "64") (name "Net-(U8B-VCAP1)") (class "Default")
      (node (ref "CK14") (pin "1") (pinfunction "1_1") (pintype "passive"))
      (node (ref "CK15") (pin "2") (pinfunction "2_2") (pintype "passive"))
      (node (ref "U8") (pin "30") (pinfunction "VCAP1_30") (pintype "passive"))
    )
    (net (code "65") (name "P_GND") (class "Default")
      (node (ref "J2") (pin "8") (pinfunction "8_8") (pintype "passive"))
      (node (ref "J3") (pin "8") (pinfunction "8_8") (pintype "passive"))
    )
    (net (code "66") (name "unconnected-(U2A-ECL-Pad6)") (class "Default")
      (node (ref "U2") (pin "6") (pinfunction "ECL_6") (pintype "passive+no_connect"))
    )
    (net (code "67") (name "unconnected-(U2A-EDA-Pad5)") (class "Default")
      (node (ref "U2") (pin "5") (pinfunction "EDA_5") (pintype "passive+no_connect"))
    )
    (net (code "68") (name "unconnected-(U2A-FSYNC-Pad10)") (class "Default")
      (node (ref "U2") (pin "10") (pinfunction "FSYNC_10") (pintype "passive+no_connect"))
    )
    (net (code "69") (name "unconnected-(U2A-INT-Pad8)") (class "Default")
      (node (ref "U2") (pin "8") (pinfunction "INT_8") (pintype "passive+no_connect"))
    )
    (net (code "70") (name "unconnected-(U3A-INT_ICM-Pad5)") (class "Default")
      (node (ref "U3") (pin "5") (pinfunction "INT_ICM_5") (pintype "passive+no_connect"))
    )
    (net (code "71") (name "unconnected-(U4A-DRDY-Pad5)") (class "Default")
      (node (ref "U4") (pin "5") (pinfunction "DRDY_5") (pintype "passive+no_connect"))
    )
    (net (code "72") (name "unconnected-(U5A-NC-Pad7)") (class "Default")
      (node (ref "U5") (pin "7") (pinfunction "NC_7") (pintype "passive+no_connect"))
    )
    (net (code "73") (name "unconnected-(U5A-SCL-Pad12)") (class "Default")
      (node (ref "U5") (pin "12") (pinfunction "SCL_12") (pintype "passive+no_connect"))
    )
    (net (code "74") (name "unconnected-(U5A-SDA-Pad11)") (class "Default")
      (node (ref "U5") (pin "11") (pinfunction "SDA_11") (pintype "passive+no_connect"))
    )
    (net (code "75") (name "unconnected-(U8A-PA8-Pad41)") (class "Default")
      (node (ref "U8") (pin "41") (pinfunction "PA8_41") (pintype "passive"))
    )
    (net (code "76") (name "unconnected-(U8A-PA10-Pad43)") (class "Default")
      (node (ref "U8") (pin "43") (pinfunction "PA10_43") (pintype "passive"))
    )
    (net (code "77") (name "unconnected-(U8A-PA15-Pad50)") (class "Default")
      (node (ref "U8") (pin "50") (pinfunction "PA15_50") (pintype "passive"))
    )
    (net (code "78") (name "unconnected-(U8A-PB4-Pad56)") (class "Default")
      (node (ref "U8") (pin "56") (pinfunction "PB4_56") (pintype "passive"))
    )
    (net (code "79") (name "unconnected-(U8A-PB5-Pad57)") (class "Default")
      (node (ref "U8") (pin "57") (pinfunction "PB5_57") (pintype "passive"))
    )
    (net (code "80") (name "unconnected-(U8A-PB10-Pad29)") (class "Default")
      (node (ref "U8") (pin "29") (pinfunction "PB10_29") (pintype "passive"))
    )
    (net (code "81") (name "unconnected-(U8A-PB12-Pad33)") (class "Default")
      (node (ref "U8") (pin "33") (pinfunction "PB12_33") (pintype "passive"))
    )
    (net (code "82") (name "unconnected-(U8A-PB13-Pad34)") (class "Default")
      (node (ref "U8") (pin "34") (pinfunction "PB13_34") (pintype "passive"))
    )
    (net (code "83") (name "unconnected-(U8A-PB14-Pad35)") (class "Default")
      (node (ref "U8") (pin "35") (pinfunction "PB14_35") (pintype "passive"))
    )
    (net (code "84") (name "unconnected-(U8A-PB15-Pad36)") (class "Default")
      (node (ref "U8") (pin "36") (pinfunction "PB15_36") (pintype "passive"))
    )
    (net (code "85") (name "unconnected-(U8A-PC5-Pad25)") (class "Default")
      (node (ref "U8") (pin "25") (pinfunction "PC5_25") (pintype "passive"))
    )
    (net (code "86") (name "unconnected-(U8A-PC6-Pad37)") (class "Default")
      (node (ref "U8") (pin "37") (pinfunction "PC6_37") (pintype "passive"))
    )
    (net (code "87") (name "unconnected-(U8A-PC7-Pad38)") (class "Default")
      (node (ref "U8") (pin "38") (pinfunction "PC7_38") (pintype "passive"))
    )
    (net (code "88") (name "unconnected-(U8A-PC8-Pad39)") (class "Default")
      (node (ref "U8") (pin "39") (pinfunction "PC8_39") (pintype "passive"))
    )
    (net (code "89") (name "unconnected-(U8A-PC9-Pad40)") (class "Default")
      (node (ref "U8") (pin "40") (pinfunction "PC9_40") (pintype "passive"))
    )
    (net (code "90") (name "unconnected-(U8A-PD2-Pad54)") (class "Default")
      (node (ref "U8") (pin "54") (pinfunction "PD2_54") (pintype "passive"))
    )
    (net (code "91") (name "unconnected-(U8B-PH0_-_OSC_IN-Pad5)") (class "Default")
      (node (ref "U8") (pin "5") (pinfunction "PH0_-_OSC_IN_5") (pintype "passive"))
    )
    (net (code "92") (name "unconnected-(U8B-PH1_-_OSC_OUT-Pad6)") (class "Default")
      (node (ref "U8") (pin "6") (pinfunction "PH1_-_OSC_OUT_6") (pintype "passive"))
    )
  )
)
